# R001B.net
KiCad netlist of a schematic drawn in EAGLE
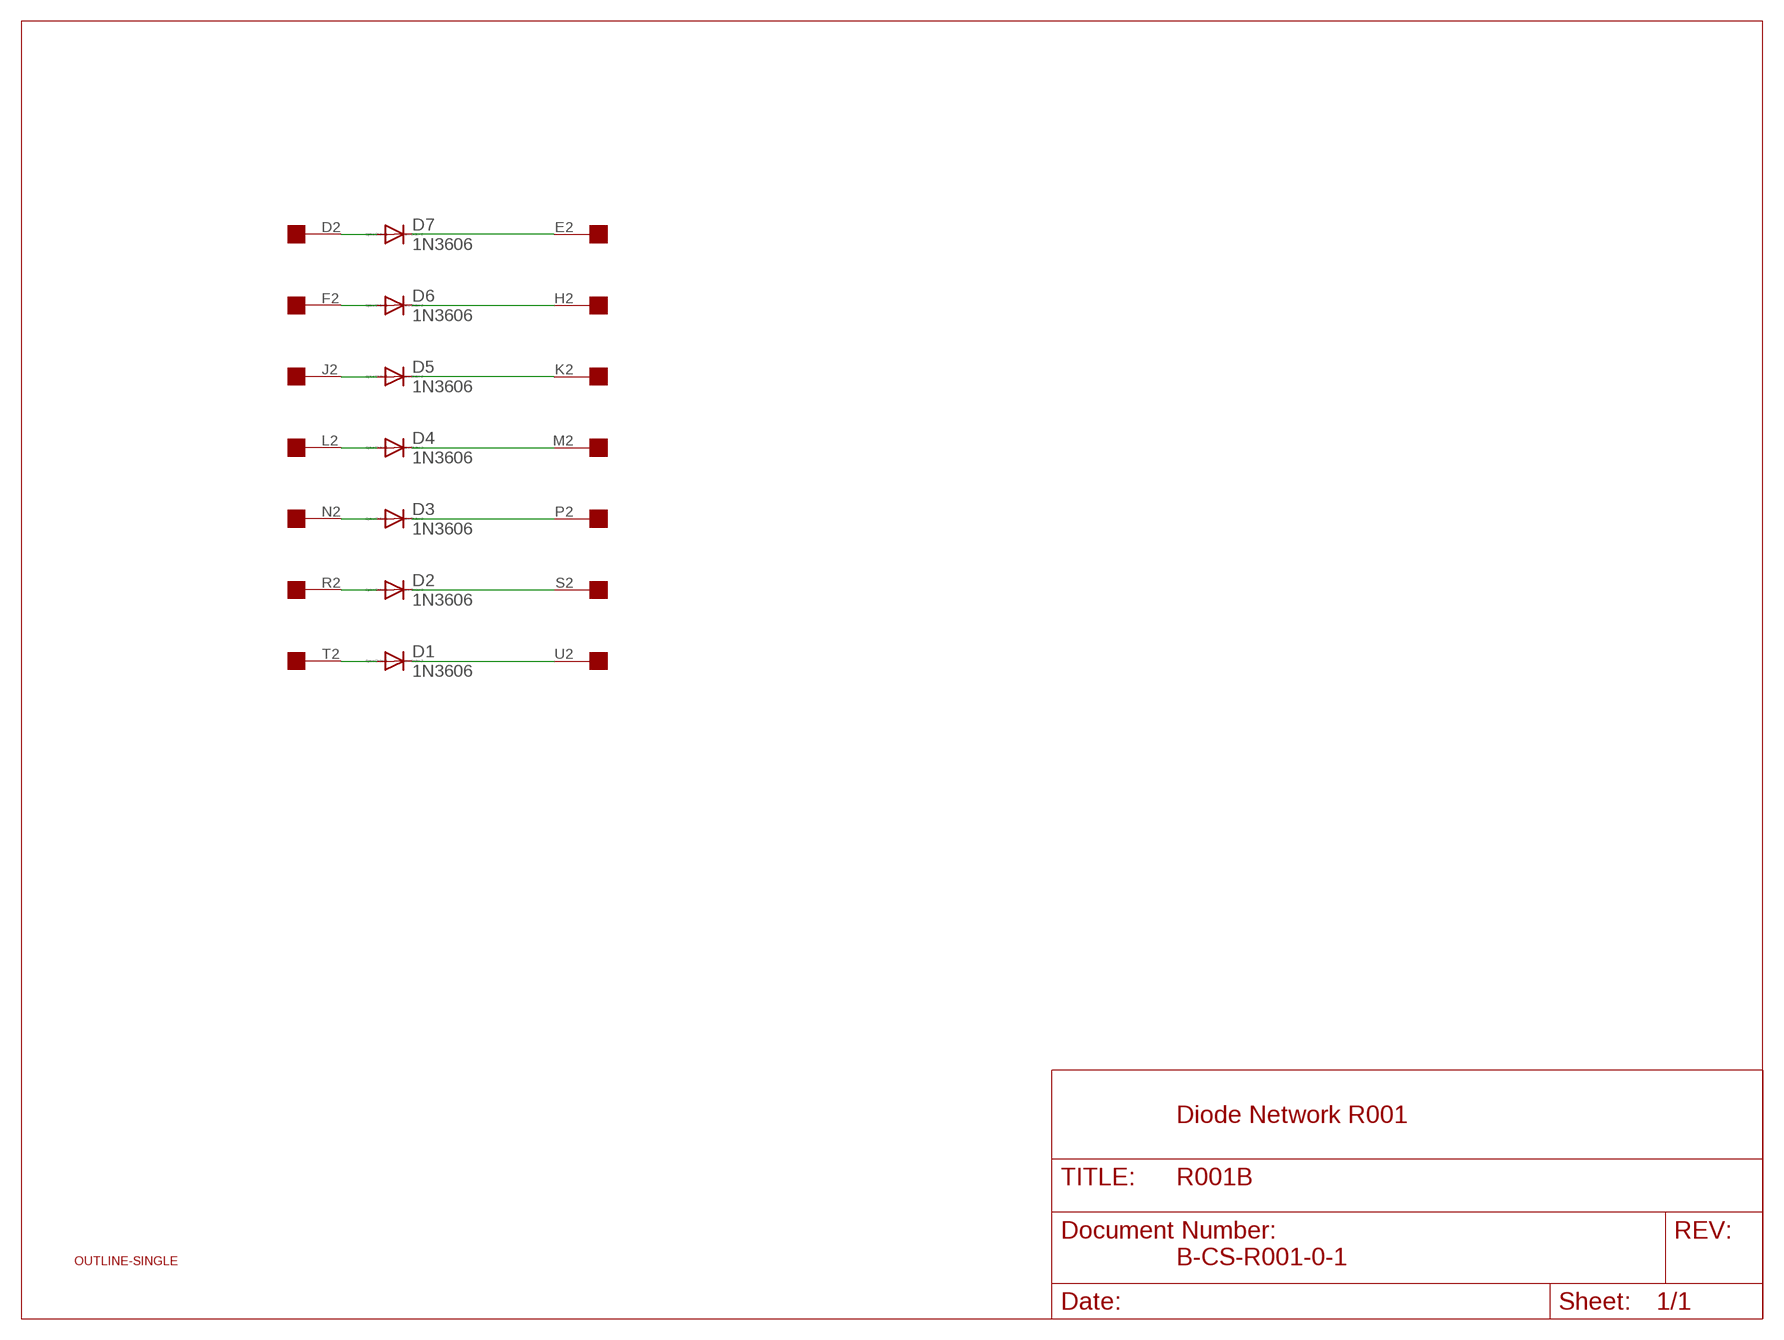
[diagram p0: schematic, sheet 1]

(export (version "E")
  (design (tool "Eeschema 10.0.6"))
  (components
    (comp (ref "D1")
      (value "1N3606")
      (footprint "eagle-import:DO35-10")
      (libsource (lib "eagle-import") (part "1N4148DO35-10"))
    )
    (comp (ref "D2")
      (value "1N3606")
      (footprint "eagle-import:DO35-10")
      (libsource (lib "eagle-import") (part "1N4148DO35-10"))
    )
    (comp (ref "D3")
      (value "1N3606")
      (footprint "eagle-import:DO35-10")
      (libsource (lib "eagle-import") (part "1N4148DO35-10"))
    )
    (comp (ref "D4")
      (value "1N3606")
      (footprint "eagle-import:DO35-10")
      (libsource (lib "eagle-import") (part "1N4148DO35-10"))
    )
    (comp (ref "D5")
      (value "1N3606")
      (footprint "eagle-import:DO35-10")
      (libsource (lib "eagle-import") (part "1N4148DO35-10"))
    )
    (comp (ref "D6")
      (value "1N3606")
      (footprint "eagle-import:DO35-10")
      (libsource (lib "eagle-import") (part "1N4148DO35-10"))
    )
    (comp (ref "D7")
      (value "1N3606")
      (footprint "eagle-import:DO35-10")
      (libsource (lib "eagle-import") (part "1N4148DO35-10"))
    )
    (comp (ref "U$1")
      (value "OUTLINE-SINGLE")
      (footprint "eagle-import:SINGLE")
      (libsource (lib "eagle-import") (part "OUTLINE-SINGLE"))
    )
    (comp (ref "U$2")
      (value "EDGE-1")
      (footprint "eagle-import:EDGE-CON1")
      (libsource (lib "eagle-import") (part "EDGE-1"))
    )
  )
  (nets
    (net (code "1") (name "Net-(U$2D-1)") (class "Default")
      (node (ref "D7") (pin "A") (pinfunction "A_A") (pintype "passive"))
      (node (ref "U$2") (pin "D2") (pinfunction "1_D2") (pintype "bidirectional"))
    )
    (net (code "2") (name "Net-(U$2E-1)") (class "Default")
      (node (ref "D7") (pin "C") (pinfunction "C_C") (pintype "passive"))
      (node (ref "U$2") (pin "E2") (pinfunction "1_E2") (pintype "bidirectional"))
    )
    (net (code "3") (name "Net-(U$2F-1)") (class "Default")
      (node (ref "D6") (pin "A") (pinfunction "A_A") (pintype "passive"))
      (node (ref "U$2") (pin "F2") (pinfunction "1_F2") (pintype "bidirectional"))
    )
    (net (code "4") (name "Net-(U$2G-1)") (class "Default")
      (node (ref "D6") (pin "C") (pinfunction "C_C") (pintype "passive"))
      (node (ref "U$2") (pin "H2") (pinfunction "1_H2") (pintype "bidirectional"))
    )
    (net (code "5") (name "Net-(U$2H-1)") (class "Default")
      (node (ref "D5") (pin "A") (pinfunction "A_A") (pintype "passive"))
      (node (ref "U$2") (pin "J2") (pinfunction "1_J2") (pintype "bidirectional"))
    )
    (net (code "6") (name "Net-(U$2I-1)") (class "Default")
      (node (ref "D5") (pin "C") (pinfunction "C_C") (pintype "passive"))
      (node (ref "U$2") (pin "K2") (pinfunction "1_K2") (pintype "bidirectional"))
    )
    (net (code "7") (name "Net-(U$2J-1)") (class "Default")
      (node (ref "D4") (pin "A") (pinfunction "A_A") (pintype "passive"))
      (node (ref "U$2") (pin "L2") (pinfunction "1_L2") (pintype "bidirectional"))
    )
    (net (code "8") (name "Net-(U$2K-1)") (class "Default")
      (node (ref "D4") (pin "C") (pinfunction "C_C") (pintype "passive"))
      (node (ref "U$2") (pin "M2") (pinfunction "1_M2") (pintype "bidirectional"))
    )
    (net (code "9") (name "Net-(U$2L-1)") (class "Default")
      (node (ref "D3") (pin "A") (pinfunction "A_A") (pintype "passive"))
      (node (ref "U$2") (pin "N2") (pinfunction "1_N2") (pintype "bidirectional"))
    )
    (net (code "10") (name "Net-(U$2M-1)") (class "Default")
      (node (ref "D3") (pin "C") (pinfunction "C_C") (pintype "passive"))
      (node (ref "U$2") (pin "P2") (pinfunction "1_P2") (pintype "bidirectional"))
    )
    (net (code "11") (name "Net-(U$2N-1)") (class "Default")
      (node (ref "D2") (pin "A") (pinfunction "A_A") (pintype "passive"))
      (node (ref "U$2") (pin "R2") (pinfunction "1_R2") (pintype "bidirectional"))
    )
    (net (code "12") (name "Net-(U$2O-1)") (class "Default")
      (node (ref "D2") (pin "C") (pinfunction "C_C") (pintype "passive"))
      (node (ref "U$2") (pin "S2") (pinfunction "1_S2") (pintype "bidirectional"))
    )
    (net (code "13") (name "Net-(U$2P-1)") (class "Default")
      (node (ref "D1") (pin "A") (pinfunction "A_A") (pintype "passive"))
      (node (ref "U$2") (pin "T2") (pinfunction "1_T2") (pintype "bidirectional"))
    )
    (net (code "14") (name "Net-(U$2Q-1)") (class "Default")
      (node (ref "D1") (pin "C") (pinfunction "C_C") (pintype "passive"))
      (node (ref "U$2") (pin "U2") (pinfunction "1_U2") (pintype "bidirectional"))
    )
  )
)
